# Projet_electronique_-_PIC-PIR_-_Groupe_5.net
KiCad netlist of a schematic drawn in EAGLE
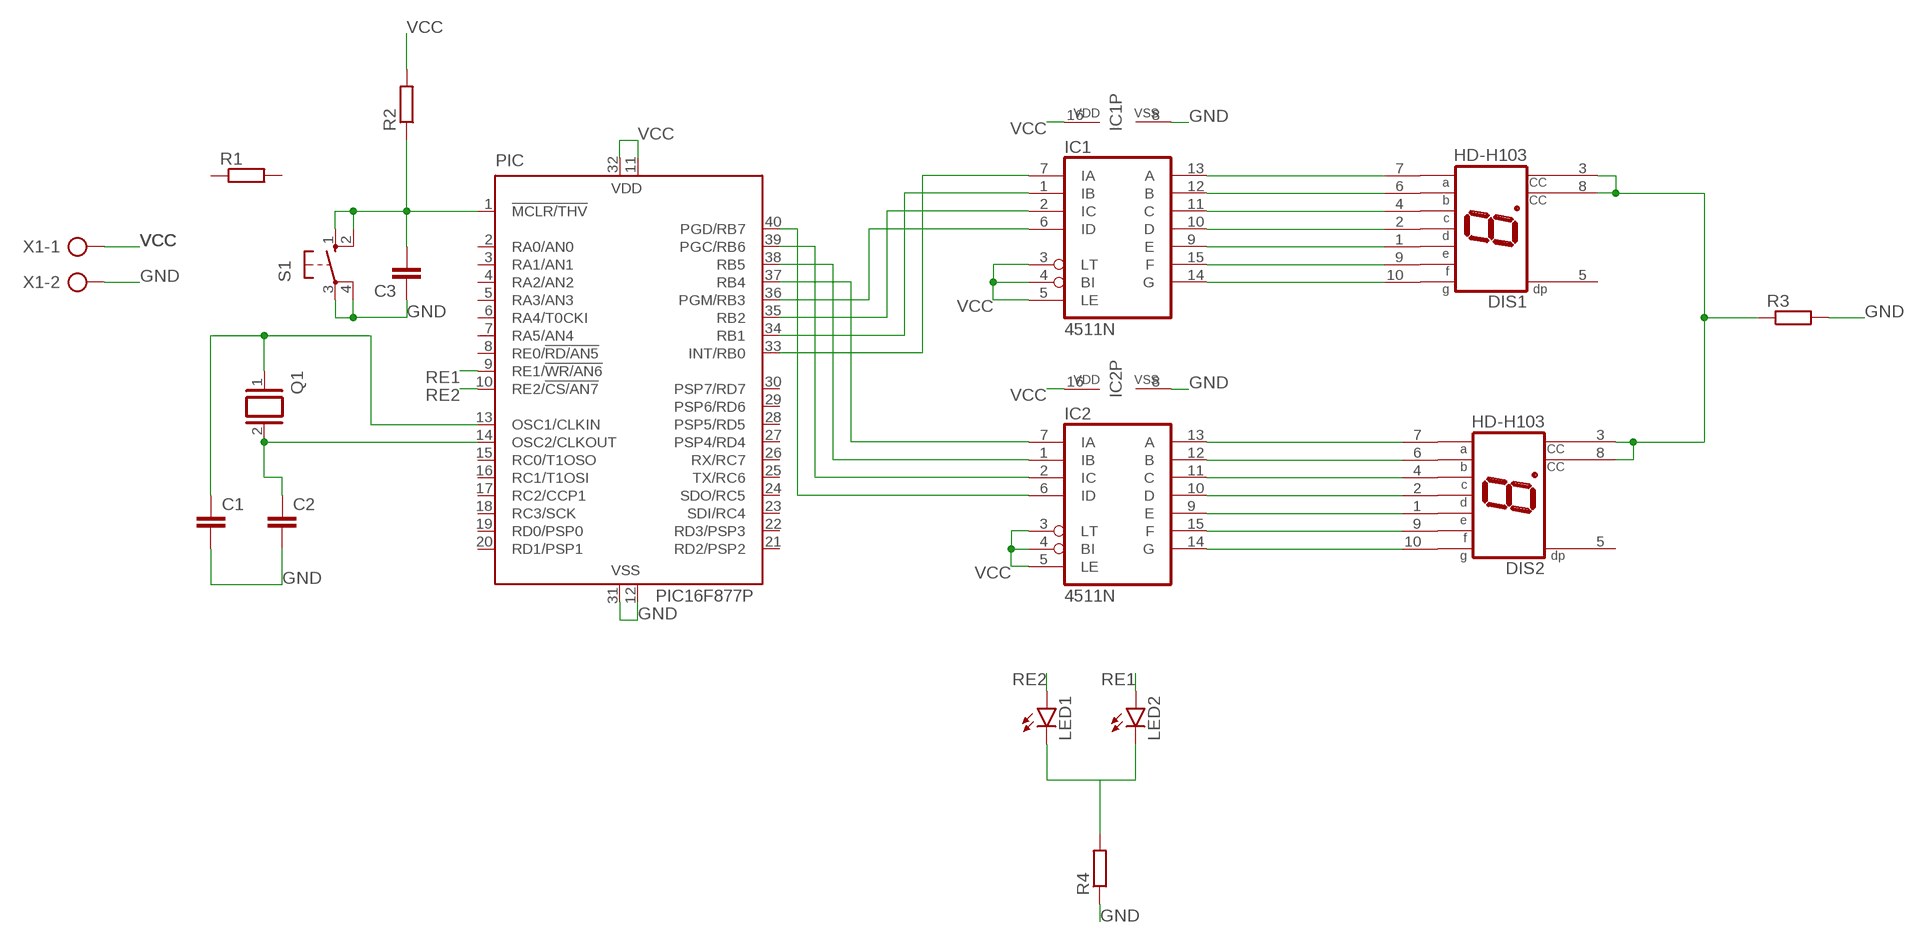
[diagram p0: schematic, sheet 1]

(export (version "E")
  (design (tool "Eeschema 10.0.6"))
  (components
    (comp (ref "C1")
      (value "C-EU025-025X050")
      (footprint "eagle-import:C025-025X050")
      (libsource (lib "eagle-import") (part "C-EU025-025X050"))
    )
    (comp (ref "C2")
      (value "C-EU025-025X050")
      (footprint "eagle-import:C025-025X050")
      (libsource (lib "eagle-import") (part "C-EU025-025X050"))
    )
    (comp (ref "C3")
      (value "C-EU025-025X050")
      (footprint "eagle-import:C025-025X050")
      (libsource (lib "eagle-import") (part "C-EU025-025X050"))
    )
    (comp (ref "DIS1")
      (value "HD-H103")
      (footprint "eagle-import:HDSP-M")
      (libsource (lib "eagle-import") (part "HD-H103"))
    )
    (comp (ref "DIS2")
      (value "HD-H103")
      (footprint "eagle-import:HDSP-M")
      (libsource (lib "eagle-import") (part "HD-H103"))
    )
    (comp (ref "IC1")
      (value "4511N")
      (footprint "eagle-import:DIL16")
      (libsource (lib "eagle-import") (part "4511N"))
    )
    (comp (ref "IC2")
      (value "4511N")
      (footprint "eagle-import:DIL16")
      (libsource (lib "eagle-import") (part "4511N"))
    )
    (comp (ref "LED1")
      (value "LED5MM")
      (footprint "eagle-import:LED5MM")
      (libsource (lib "eagle-import") (part "LED5MM"))
    )
    (comp (ref "LED2")
      (value "LED5MM")
      (footprint "eagle-import:LED5MM")
      (libsource (lib "eagle-import") (part "LED5MM"))
    )
    (comp (ref "PIC")
      (value "PIC16F877P")
      (footprint "eagle-import:DIL40")
      (fields (field (name "MF") "MICROCHIP") (field (name "MPN") "PIC16F877-04/P"))
      (libsource (lib "eagle-import") (part "PIC16F87P7"))
    )
    (comp (ref "Q1")
      (value "XTAL/S")
      (footprint "eagle-import:QS")
      (libsource (lib "eagle-import") (part "XTAL/S"))
    )
    (comp (ref "R1")
      (value "R-EU_0207/10")
      (footprint "eagle-import:0207_10")
      (libsource (lib "eagle-import") (part "R-EU_0207/10"))
    )
    (comp (ref "R2")
      (value "R-EU_0207/10")
      (footprint "eagle-import:0207_10")
      (libsource (lib "eagle-import") (part "R-EU_0207/10"))
    )
    (comp (ref "R3")
      (value "R-EU_0207/10")
      (footprint "eagle-import:0207_10")
      (libsource (lib "eagle-import") (part "R-EU_0207/10"))
    )
    (comp (ref "R4")
      (value "R-EU_0207/10")
      (footprint "eagle-import:0207_10")
      (libsource (lib "eagle-import") (part "R-EU_0207/10"))
    )
    (comp (ref "S1")
      (value "10-XX")
      (footprint "eagle-import:B3F-10XX")
      (fields (field (name "MPN") "B3F-1000"))
      (libsource (lib "eagle-import") (part "10-XX"))
    )
    (comp (ref "X1")
      (value "AK300/2")
      (footprint "eagle-import:AK300_2")
      (libsource (lib "eagle-import") (part "AK300/2"))
    )
  )
  (nets
    (net (code "1") (name "/GND") (class "Default")
      (node (ref "C1") (pin "2") (pinfunction "2_2") (pintype "passive"))
      (node (ref "C2") (pin "2") (pinfunction "2_2") (pintype "passive"))
      (node (ref "C3") (pin "1") (pinfunction "1_1") (pintype "passive"))
      (node (ref "IC1") (pin "8") (pinfunction "VSS_8") (pintype "power_in"))
      (node (ref "IC2") (pin "8") (pinfunction "VSS_8") (pintype "power_in"))
      (node (ref "PIC") (pin "12") (pinfunction "VSS_12") (pintype "power_in"))
      (node (ref "PIC") (pin "31") (pinfunction "VSS_31") (pintype "power_in"))
      (node (ref "R3") (pin "2") (pinfunction "2_2") (pintype "passive"))
      (node (ref "R4") (pin "1") (pinfunction "1_1") (pintype "passive"))
      (node (ref "S1") (pin "3") (pinfunction "P_3") (pintype "passive"))
      (node (ref "S1") (pin "4") (pinfunction "P1_4") (pintype "passive"))
      (node (ref "X1") (pin "2") (pinfunction "KL_2") (pintype "passive"))
    )
    (net (code "2") (name "/RE1") (class "Default")
      (node (ref "LED2") (pin "A") (pinfunction "A_A") (pintype "passive"))
      (node (ref "PIC") (pin "9") (pinfunction "RE1/~{WR/AN6}_9") (pintype "bidirectional"))
    )
    (net (code "3") (name "/RE2") (class "Default")
      (node (ref "LED1") (pin "A") (pinfunction "A_A") (pintype "passive"))
      (node (ref "PIC") (pin "10") (pinfunction "RE2/~{CS/AN7}_10") (pintype "bidirectional"))
    )
    (net (code "4") (name "/VCC") (class "Default")
      (node (ref "IC1") (pin "16") (pinfunction "VDD_16") (pintype "power_in"))
      (node (ref "IC1") (pin "3") (pinfunction "LT_3") (pintype "input"))
      (node (ref "IC1") (pin "4") (pinfunction "BI_4") (pintype "input"))
      (node (ref "IC1") (pin "5") (pinfunction "LE_5") (pintype "input"))
      (node (ref "IC2") (pin "16") (pinfunction "VDD_16") (pintype "power_in"))
      (node (ref "IC2") (pin "3") (pinfunction "LT_3") (pintype "input"))
      (node (ref "IC2") (pin "4") (pinfunction "BI_4") (pintype "input"))
      (node (ref "IC2") (pin "5") (pinfunction "LE_5") (pintype "input"))
      (node (ref "PIC") (pin "11") (pinfunction "VDD_11") (pintype "power_in"))
      (node (ref "PIC") (pin "32") (pinfunction "VDD_32") (pintype "power_in"))
      (node (ref "R2") (pin "2") (pinfunction "2_2") (pintype "passive"))
      (node (ref "X1") (pin "1") (pinfunction "KL_1") (pintype "passive"))
    )
    (net (code "5") (name "Net-(DIS1-A)") (class "Default")
      (node (ref "DIS1") (pin "7") (pinfunction "A_7") (pintype "passive"))
      (node (ref "IC1") (pin "13") (pinfunction "A_13") (pintype "output"))
    )
    (net (code "6") (name "Net-(DIS1-B)") (class "Default")
      (node (ref "DIS1") (pin "6") (pinfunction "B_6") (pintype "passive"))
      (node (ref "IC1") (pin "12") (pinfunction "B_12") (pintype "output"))
    )
    (net (code "7") (name "Net-(DIS1-C)") (class "Default")
      (node (ref "DIS1") (pin "4") (pinfunction "C_4") (pintype "passive"))
      (node (ref "IC1") (pin "11") (pinfunction "C_11") (pintype "output"))
    )
    (net (code "8") (name "Net-(DIS1-CC-Pad3)") (class "Default")
      (node (ref "DIS1") (pin "3") (pinfunction "CC_3") (pintype "passive"))
      (node (ref "DIS1") (pin "8") (pinfunction "CC_8") (pintype "passive"))
      (node (ref "DIS2") (pin "3") (pinfunction "CC_3") (pintype "passive"))
      (node (ref "DIS2") (pin "8") (pinfunction "CC_8") (pintype "passive"))
      (node (ref "R3") (pin "1") (pinfunction "1_1") (pintype "passive"))
    )
    (net (code "9") (name "Net-(DIS1-D)") (class "Default")
      (node (ref "DIS1") (pin "2") (pinfunction "D_2") (pintype "passive"))
      (node (ref "IC1") (pin "10") (pinfunction "D_10") (pintype "output"))
    )
    (net (code "10") (name "Net-(DIS1-E)") (class "Default")
      (node (ref "DIS1") (pin "1") (pinfunction "E_1") (pintype "passive"))
      (node (ref "IC1") (pin "9") (pinfunction "E_9") (pintype "output"))
    )
    (net (code "11") (name "Net-(DIS1-F)") (class "Default")
      (node (ref "DIS1") (pin "9") (pinfunction "F_9") (pintype "passive"))
      (node (ref "IC1") (pin "15") (pinfunction "F_15") (pintype "output"))
    )
    (net (code "12") (name "Net-(DIS1-G)") (class "Default")
      (node (ref "DIS1") (pin "10") (pinfunction "G_10") (pintype "passive"))
      (node (ref "IC1") (pin "14") (pinfunction "G_14") (pintype "output"))
    )
    (net (code "13") (name "Net-(DIS2-A)") (class "Default")
      (node (ref "DIS2") (pin "7") (pinfunction "A_7") (pintype "passive"))
      (node (ref "IC2") (pin "13") (pinfunction "A_13") (pintype "output"))
    )
    (net (code "14") (name "Net-(DIS2-B)") (class "Default")
      (node (ref "DIS2") (pin "6") (pinfunction "B_6") (pintype "passive"))
      (node (ref "IC2") (pin "12") (pinfunction "B_12") (pintype "output"))
    )
    (net (code "15") (name "Net-(DIS2-C)") (class "Default")
      (node (ref "DIS2") (pin "4") (pinfunction "C_4") (pintype "passive"))
      (node (ref "IC2") (pin "11") (pinfunction "C_11") (pintype "output"))
    )
    (net (code "16") (name "Net-(DIS2-D)") (class "Default")
      (node (ref "DIS2") (pin "2") (pinfunction "D_2") (pintype "passive"))
      (node (ref "IC2") (pin "10") (pinfunction "D_10") (pintype "output"))
    )
    (net (code "17") (name "Net-(DIS2-E)") (class "Default")
      (node (ref "DIS2") (pin "1") (pinfunction "E_1") (pintype "passive"))
      (node (ref "IC2") (pin "9") (pinfunction "E_9") (pintype "output"))
    )
    (net (code "18") (name "Net-(DIS2-F)") (class "Default")
      (node (ref "DIS2") (pin "9") (pinfunction "F_9") (pintype "passive"))
      (node (ref "IC2") (pin "15") (pinfunction "F_15") (pintype "output"))
    )
    (net (code "19") (name "Net-(DIS2-G)") (class "Default")
      (node (ref "DIS2") (pin "10") (pinfunction "G_10") (pintype "passive"))
      (node (ref "IC2") (pin "14") (pinfunction "G_14") (pintype "output"))
    )
    (net (code "20") (name "Net-(IC1A-IA)") (class "Default")
      (node (ref "IC1") (pin "7") (pinfunction "IA_7") (pintype "input"))
      (node (ref "PIC") (pin "33") (pinfunction "INT/RB0_33") (pintype "bidirectional"))
    )
    (net (code "21") (name "Net-(IC1A-IB)") (class "Default")
      (node (ref "IC1") (pin "1") (pinfunction "IB_1") (pintype "input"))
      (node (ref "PIC") (pin "34") (pinfunction "RB1_34") (pintype "bidirectional"))
    )
    (net (code "22") (name "Net-(IC1A-IC)") (class "Default")
      (node (ref "IC1") (pin "2") (pinfunction "IC_2") (pintype "input"))
      (node (ref "PIC") (pin "35") (pinfunction "RB2_35") (pintype "bidirectional"))
    )
    (net (code "23") (name "Net-(IC1A-ID)") (class "Default")
      (node (ref "IC1") (pin "6") (pinfunction "ID_6") (pintype "input"))
      (node (ref "PIC") (pin "36") (pinfunction "PGM/RB3_36") (pintype "bidirectional"))
    )
    (net (code "24") (name "Net-(IC2A-IA)") (class "Default")
      (node (ref "IC2") (pin "7") (pinfunction "IA_7") (pintype "input"))
      (node (ref "PIC") (pin "37") (pinfunction "RB4_37") (pintype "bidirectional"))
    )
    (net (code "25") (name "Net-(IC2A-IB)") (class "Default")
      (node (ref "IC2") (pin "1") (pinfunction "IB_1") (pintype "input"))
      (node (ref "PIC") (pin "38") (pinfunction "RB5_38") (pintype "bidirectional"))
    )
    (net (code "26") (name "Net-(IC2A-IC)") (class "Default")
      (node (ref "IC2") (pin "2") (pinfunction "IC_2") (pintype "input"))
      (node (ref "PIC") (pin "39") (pinfunction "PGC/RB6_39") (pintype "bidirectional"))
    )
    (net (code "27") (name "Net-(IC2A-ID)") (class "Default")
      (node (ref "IC2") (pin "6") (pinfunction "ID_6") (pintype "input"))
      (node (ref "PIC") (pin "40") (pinfunction "PGD/RB7_40") (pintype "bidirectional"))
    )
    (net (code "28") (name "Net-(LED1-C)") (class "Default")
      (node (ref "LED1") (pin "K") (pinfunction "C_K") (pintype "passive"))
      (node (ref "LED2") (pin "K") (pinfunction "C_K") (pintype "passive"))
      (node (ref "R4") (pin "2") (pinfunction "2_2") (pintype "passive"))
    )
    (net (code "29") (name "Net-(PIC-OSC1{slash}CLKIN)") (class "Default")
      (node (ref "C1") (pin "1") (pinfunction "1_1") (pintype "passive"))
      (node (ref "PIC") (pin "13") (pinfunction "OSC1/CLKIN_13") (pintype "input"))
      (node (ref "Q1") (pin "1") (pinfunction "1_1") (pintype "passive"))
    )
    (net (code "30") (name "Net-(PIC-OSC2{slash}CLKOUT)") (class "Default")
      (node (ref "C2") (pin "1") (pinfunction "1_1") (pintype "passive"))
      (node (ref "PIC") (pin "14") (pinfunction "OSC2/CLKOUT_14") (pintype "output"))
      (node (ref "Q1") (pin "2") (pinfunction "2_2") (pintype "passive"))
    )
    (net (code "31") (name "Net-(PIC-~{MCLR{slash}THV})") (class "Default")
      (node (ref "C3") (pin "2") (pinfunction "2_2") (pintype "passive"))
      (node (ref "PIC") (pin "1") (pinfunction "~{MCLR/THV}_1") (pintype "input"))
      (node (ref "R2") (pin "1") (pinfunction "1_1") (pintype "passive"))
      (node (ref "S1") (pin "1") (pinfunction "S_1") (pintype "passive"))
      (node (ref "S1") (pin "2") (pinfunction "S1_2") (pintype "passive"))
    )
    (net (code "32") (name "unconnected-(DIS1-DP-Pad5)") (class "Default")
      (node (ref "DIS1") (pin "5") (pinfunction "DP_5") (pintype "passive"))
    )
    (net (code "33") (name "unconnected-(DIS2-DP-Pad5)") (class "Default")
      (node (ref "DIS2") (pin "5") (pinfunction "DP_5") (pintype "passive"))
    )
    (net (code "34") (name "unconnected-(PIC-PSP4{slash}RD4-Pad27)") (class "Default")
      (node (ref "PIC") (pin "27") (pinfunction "PSP4/RD4_27") (pintype "bidirectional"))
    )
    (net (code "35") (name "unconnected-(PIC-PSP5{slash}RD5-Pad28)") (class "Default")
      (node (ref "PIC") (pin "28") (pinfunction "PSP5/RD5_28") (pintype "bidirectional"))
    )
    (net (code "36") (name "unconnected-(PIC-PSP6{slash}RD6-Pad29)") (class "Default")
      (node (ref "PIC") (pin "29") (pinfunction "PSP6/RD6_29") (pintype "bidirectional"))
    )
    (net (code "37") (name "unconnected-(PIC-PSP7{slash}RD7-Pad30)") (class "Default")
      (node (ref "PIC") (pin "30") (pinfunction "PSP7/RD7_30") (pintype "bidirectional"))
    )
    (net (code "38") (name "unconnected-(PIC-RA0{slash}AN0-Pad2)") (class "Default")
      (node (ref "PIC") (pin "2") (pinfunction "RA0/AN0_2") (pintype "bidirectional"))
    )
    (net (code "39") (name "unconnected-(PIC-RA1{slash}AN1-Pad3)") (class "Default")
      (node (ref "PIC") (pin "3") (pinfunction "RA1/AN1_3") (pintype "bidirectional"))
    )
    (net (code "40") (name "unconnected-(PIC-RA2{slash}AN2-Pad4)") (class "Default")
      (node (ref "PIC") (pin "4") (pinfunction "RA2/AN2_4") (pintype "bidirectional"))
    )
    (net (code "41") (name "unconnected-(PIC-RA3{slash}AN3-Pad5)") (class "Default")
      (node (ref "PIC") (pin "5") (pinfunction "RA3/AN3_5") (pintype "bidirectional"))
    )
    (net (code "42") (name "unconnected-(PIC-RA4{slash}T0CKI-Pad6)") (class "Default")
      (node (ref "PIC") (pin "6") (pinfunction "RA4/T0CKI_6") (pintype "bidirectional"))
    )
    (net (code "43") (name "unconnected-(PIC-RA5{slash}AN4-Pad7)") (class "Default")
      (node (ref "PIC") (pin "7") (pinfunction "RA5/AN4_7") (pintype "bidirectional"))
    )
    (net (code "44") (name "unconnected-(PIC-RC0{slash}T1OSO-Pad15)") (class "Default")
      (node (ref "PIC") (pin "15") (pinfunction "RC0/T1OSO_15") (pintype "bidirectional"))
    )
    (net (code "45") (name "unconnected-(PIC-RC1{slash}T1OSI-Pad16)") (class "Default")
      (node (ref "PIC") (pin "16") (pinfunction "RC1/T1OSI_16") (pintype "bidirectional"))
    )
    (net (code "46") (name "unconnected-(PIC-RC2{slash}CCP1-Pad17)") (class "Default")
      (node (ref "PIC") (pin "17") (pinfunction "RC2/CCP1_17") (pintype "bidirectional"))
    )
    (net (code "47") (name "unconnected-(PIC-RC3{slash}SCK-Pad18)") (class "Default")
      (node (ref "PIC") (pin "18") (pinfunction "RC3/SCK_18") (pintype "bidirectional"))
    )
    (net (code "48") (name "unconnected-(PIC-RD0{slash}PSP0-Pad19)") (class "Default")
      (node (ref "PIC") (pin "19") (pinfunction "RD0/PSP0_19") (pintype "bidirectional"))
    )
    (net (code "49") (name "unconnected-(PIC-RD1{slash}PSP1-Pad20)") (class "Default")
      (node (ref "PIC") (pin "20") (pinfunction "RD1/PSP1_20") (pintype "bidirectional"))
    )
    (net (code "50") (name "unconnected-(PIC-RD2{slash}PSP2-Pad21)") (class "Default")
      (node (ref "PIC") (pin "21") (pinfunction "RD2/PSP2_21") (pintype "bidirectional"))
    )
    (net (code "51") (name "unconnected-(PIC-RD3{slash}PSP3-Pad22)") (class "Default")
      (node (ref "PIC") (pin "22") (pinfunction "RD3/PSP3_22") (pintype "bidirectional"))
    )
    (net (code "52") (name "unconnected-(PIC-RE0{slash}~{RD{slash}AN5}-Pad8)") (class "Default")
      (node (ref "PIC") (pin "8") (pinfunction "RE0/~{RD/AN5}_8") (pintype "bidirectional"))
    )
    (net (code "53") (name "unconnected-(PIC-RX{slash}RC7-Pad26)") (class "Default")
      (node (ref "PIC") (pin "26") (pinfunction "RX/RC7_26") (pintype "bidirectional"))
    )
    (net (code "54") (name "unconnected-(PIC-SDI{slash}RC4-Pad23)") (class "Default")
      (node (ref "PIC") (pin "23") (pinfunction "SDI/RC4_23") (pintype "bidirectional"))
    )
    (net (code "55") (name "unconnected-(PIC-SDO{slash}RC5-Pad24)") (class "Default")
      (node (ref "PIC") (pin "24") (pinfunction "SDO/RC5_24") (pintype "bidirectional"))
    )
    (net (code "56") (name "unconnected-(PIC-TX{slash}RC6-Pad25)") (class "Default")
      (node (ref "PIC") (pin "25") (pinfunction "TX/RC6_25") (pintype "bidirectional"))
    )
    (net (code "57") (name "unconnected-(R1-Pad1)") (class "Default")
      (node (ref "R1") (pin "1") (pinfunction "1_1") (pintype "passive"))
    )
    (net (code "58") (name "unconnected-(R1-Pad2)") (class "Default")
      (node (ref "R1") (pin "2") (pinfunction "2_2") (pintype "passive"))
    )
  )
)
